# Board.net
KiCad netlist of a schematic drawn in EAGLE
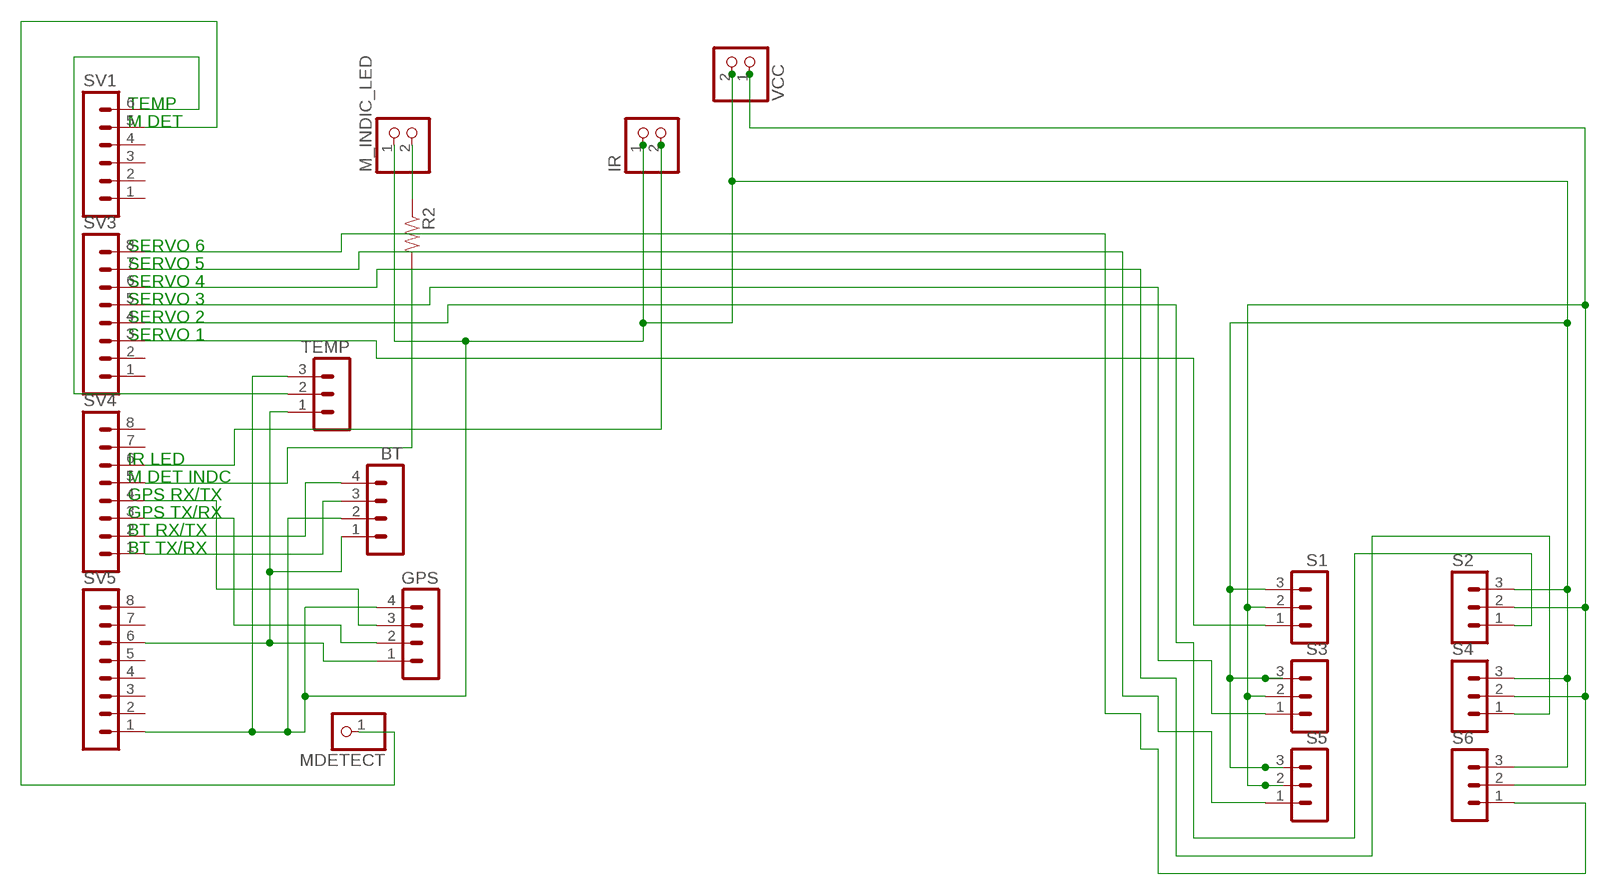
[diagram p0: schematic, sheet 1]

(export (version "E")
  (design (tool "Eeschema 10.0.6"))
  (components
    (comp (ref "BT")
      (value "MA04-1")
      (footprint "eagle-import:MA04-1")
      (libsource (lib "eagle-import") (part "MA04-1"))
    )
    (comp (ref "GPS")
      (value "MA04-1")
      (footprint "eagle-import:MA04-1")
      (libsource (lib "eagle-import") (part "MA04-1"))
    )
    (comp (ref "IR")
      (value "PINHD-1X2")
      (footprint "eagle-import:1X02")
      (libsource (lib "eagle-import") (part "PINHD-1X2"))
    )
    (comp (ref "MDETECT")
      (value "PINHD-1X1")
      (footprint "eagle-import:1X01")
      (libsource (lib "eagle-import") (part "PINHD-1X1"))
    )
    (comp (ref "M_INDIC_LED")
      (value "PINHD-1X2")
      (footprint "eagle-import:1X02")
      (libsource (lib "eagle-import") (part "PINHD-1X2"))
    )
    (comp (ref "R2")
      (value "RESISTORAXIAL-0.3")
      (footprint "eagle-import:AXIAL-0.3")
      (libsource (lib "eagle-import") (part "RESISTORAXIAL-0.3"))
    )
    (comp (ref "S1")
      (value "MA03-1")
      (footprint "eagle-import:MA03-1")
      (libsource (lib "eagle-import") (part "MA03-1"))
    )
    (comp (ref "S2")
      (value "MA03-1")
      (footprint "eagle-import:MA03-1")
      (libsource (lib "eagle-import") (part "MA03-1"))
    )
    (comp (ref "S3")
      (value "MA03-1")
      (footprint "eagle-import:MA03-1")
      (libsource (lib "eagle-import") (part "MA03-1"))
    )
    (comp (ref "S4")
      (value "MA03-1")
      (footprint "eagle-import:MA03-1")
      (libsource (lib "eagle-import") (part "MA03-1"))
    )
    (comp (ref "S5")
      (value "MA03-1")
      (footprint "eagle-import:MA03-1")
      (libsource (lib "eagle-import") (part "MA03-1"))
    )
    (comp (ref "S6")
      (value "MA03-1")
      (footprint "eagle-import:MA03-1")
      (libsource (lib "eagle-import") (part "MA03-1"))
    )
    (comp (ref "SV1")
      (value "MA06-1")
      (footprint "eagle-import:MA06-1")
      (libsource (lib "eagle-import") (part "MA06-1"))
    )
    (comp (ref "SV3")
      (value "MA08-1")
      (footprint "eagle-import:MA08-1")
      (libsource (lib "eagle-import") (part "MA08-1"))
    )
    (comp (ref "SV4")
      (value "MA08-1")
      (footprint "eagle-import:MA08-1")
      (libsource (lib "eagle-import") (part "MA08-1"))
    )
    (comp (ref "SV5")
      (value "MA08-1")
      (footprint "eagle-import:MA08-1")
      (libsource (lib "eagle-import") (part "MA08-1"))
    )
    (comp (ref "TEMP")
      (value "MA03-1")
      (footprint "eagle-import:MA03-1")
      (libsource (lib "eagle-import") (part "MA03-1"))
    )
    (comp (ref "VCC")
      (value "PINHD-1X2")
      (footprint "eagle-import:1X02")
      (libsource (lib "eagle-import") (part "PINHD-1X2"))
    )
  )
  (nets
    (net (code "1") (name "Net-(BT-Pad1)") (class "Default")
      (node (ref "BT") (pin "1") (pinfunction "1_1") (pintype "passive"))
      (node (ref "GPS") (pin "1") (pinfunction "1_1") (pintype "passive"))
      (node (ref "SV5") (pin "6") (pinfunction "6_6") (pintype "passive"))
      (node (ref "TEMP") (pin "1") (pinfunction "1_1") (pintype "passive"))
    )
    (net (code "2") (name "Net-(BT-Pad2)") (class "Default")
      (node (ref "BT") (pin "2") (pinfunction "2_2") (pintype "passive"))
      (node (ref "GPS") (pin "4") (pinfunction "4_4") (pintype "passive"))
      (node (ref "IR") (pin "1") (pinfunction "1_1") (pintype "passive"))
      (node (ref "M_INDIC_LED") (pin "1") (pinfunction "1_1") (pintype "passive"))
      (node (ref "S1") (pin "3") (pinfunction "3_3") (pintype "passive"))
      (node (ref "S2") (pin "3") (pinfunction "3_3") (pintype "passive"))
      (node (ref "S3") (pin "3") (pinfunction "3_3") (pintype "passive"))
      (node (ref "S4") (pin "3") (pinfunction "3_3") (pintype "passive"))
      (node (ref "S5") (pin "3") (pinfunction "3_3") (pintype "passive"))
      (node (ref "S6") (pin "3") (pinfunction "3_3") (pintype "passive"))
      (node (ref "SV5") (pin "1") (pinfunction "1_1") (pintype "passive"))
      (node (ref "TEMP") (pin "3") (pinfunction "3_3") (pintype "passive"))
      (node (ref "VCC") (pin "2") (pinfunction "2_2") (pintype "passive"))
    )
    (net (code "3") (name "Net-(BT-Pad3)") (class "Default")
      (node (ref "BT") (pin "3") (pinfunction "3_3") (pintype "passive"))
      (node (ref "SV4") (pin "1") (pinfunction "1_1") (pintype "passive"))
    )
    (net (code "4") (name "Net-(BT-Pad4)") (class "Default")
      (node (ref "BT") (pin "4") (pinfunction "4_4") (pintype "passive"))
      (node (ref "SV4") (pin "2") (pinfunction "2_2") (pintype "passive"))
    )
    (net (code "5") (name "Net-(GPS-Pad2)") (class "Default")
      (node (ref "GPS") (pin "2") (pinfunction "2_2") (pintype "passive"))
      (node (ref "SV4") (pin "3") (pinfunction "3_3") (pintype "passive"))
    )
    (net (code "6") (name "Net-(GPS-Pad3)") (class "Default")
      (node (ref "GPS") (pin "3") (pinfunction "3_3") (pintype "passive"))
      (node (ref "SV4") (pin "4") (pinfunction "4_4") (pintype "passive"))
    )
    (net (code "7") (name "Net-(IR-Pad2)") (class "Default")
      (node (ref "IR") (pin "2") (pinfunction "2_2") (pintype "passive"))
      (node (ref "SV4") (pin "6") (pinfunction "6_6") (pintype "passive"))
    )
    (net (code "8") (name "Net-(MDETECT-Pad1)") (class "Default")
      (node (ref "MDETECT") (pin "1") (pinfunction "1_1") (pintype "passive"))
      (node (ref "SV1") (pin "5") (pinfunction "5_5") (pintype "passive"))
    )
    (net (code "9") (name "Net-(R2-1)") (class "Default")
      (node (ref "M_INDIC_LED") (pin "2") (pinfunction "2_2") (pintype "passive"))
      (node (ref "R2") (pin "P$1") (pinfunction "1_P$1") (pintype "passive"))
    )
    (net (code "10") (name "Net-(R2-2)") (class "Default")
      (node (ref "R2") (pin "P$2") (pinfunction "2_P$2") (pintype "passive"))
      (node (ref "SV4") (pin "5") (pinfunction "5_5") (pintype "passive"))
    )
    (net (code "11") (name "Net-(S1-Pad1)") (class "Default")
      (node (ref "S1") (pin "1") (pinfunction "1_1") (pintype "passive"))
      (node (ref "SV3") (pin "3") (pinfunction "3_3") (pintype "passive"))
    )
    (net (code "12") (name "Net-(S1-Pad2)") (class "Default")
      (node (ref "S1") (pin "2") (pinfunction "2_2") (pintype "passive"))
      (node (ref "S2") (pin "2") (pinfunction "2_2") (pintype "passive"))
      (node (ref "S3") (pin "2") (pinfunction "2_2") (pintype "passive"))
      (node (ref "S4") (pin "2") (pinfunction "2_2") (pintype "passive"))
      (node (ref "S5") (pin "2") (pinfunction "2_2") (pintype "passive"))
      (node (ref "S6") (pin "2") (pinfunction "2_2") (pintype "passive"))
      (node (ref "VCC") (pin "1") (pinfunction "1_1") (pintype "passive"))
    )
    (net (code "13") (name "Net-(S2-Pad1)") (class "Default")
      (node (ref "S2") (pin "1") (pinfunction "1_1") (pintype "passive"))
      (node (ref "SV3") (pin "4") (pinfunction "4_4") (pintype "passive"))
    )
    (net (code "14") (name "Net-(S3-Pad1)") (class "Default")
      (node (ref "S3") (pin "1") (pinfunction "1_1") (pintype "passive"))
      (node (ref "SV3") (pin "5") (pinfunction "5_5") (pintype "passive"))
    )
    (net (code "15") (name "Net-(S4-Pad1)") (class "Default")
      (node (ref "S4") (pin "1") (pinfunction "1_1") (pintype "passive"))
      (node (ref "SV3") (pin "6") (pinfunction "6_6") (pintype "passive"))
    )
    (net (code "16") (name "Net-(S5-Pad1)") (class "Default")
      (node (ref "S5") (pin "1") (pinfunction "1_1") (pintype "passive"))
      (node (ref "SV3") (pin "7") (pinfunction "7_7") (pintype "passive"))
    )
    (net (code "17") (name "Net-(S6-Pad1)") (class "Default")
      (node (ref "S6") (pin "1") (pinfunction "1_1") (pintype "passive"))
      (node (ref "SV3") (pin "8") (pinfunction "8_8") (pintype "passive"))
    )
    (net (code "18") (name "Net-(SV1-Pad6)") (class "Default")
      (node (ref "SV1") (pin "6") (pinfunction "6_6") (pintype "passive"))
      (node (ref "TEMP") (pin "2") (pinfunction "2_2") (pintype "passive"))
    )
    (net (code "19") (name "unconnected-(SV1-Pad1)") (class "Default")
      (node (ref "SV1") (pin "1") (pinfunction "1_1") (pintype "passive"))
    )
    (net (code "20") (name "unconnected-(SV1-Pad2)") (class "Default")
      (node (ref "SV1") (pin "2") (pinfunction "2_2") (pintype "passive"))
    )
    (net (code "21") (name "unconnected-(SV1-Pad3)") (class "Default")
      (node (ref "SV1") (pin "3") (pinfunction "3_3") (pintype "passive"))
    )
    (net (code "22") (name "unconnected-(SV1-Pad4)") (class "Default")
      (node (ref "SV1") (pin "4") (pinfunction "4_4") (pintype "passive"))
    )
    (net (code "23") (name "unconnected-(SV3-Pad1)") (class "Default")
      (node (ref "SV3") (pin "1") (pinfunction "1_1") (pintype "passive"))
    )
    (net (code "24") (name "unconnected-(SV3-Pad2)") (class "Default")
      (node (ref "SV3") (pin "2") (pinfunction "2_2") (pintype "passive"))
    )
    (net (code "25") (name "unconnected-(SV4-Pad7)") (class "Default")
      (node (ref "SV4") (pin "7") (pinfunction "7_7") (pintype "passive"))
    )
    (net (code "26") (name "unconnected-(SV4-Pad8)") (class "Default")
      (node (ref "SV4") (pin "8") (pinfunction "8_8") (pintype "passive"))
    )
    (net (code "27") (name "unconnected-(SV5-Pad2)") (class "Default")
      (node (ref "SV5") (pin "2") (pinfunction "2_2") (pintype "passive"))
    )
    (net (code "28") (name "unconnected-(SV5-Pad3)") (class "Default")
      (node (ref "SV5") (pin "3") (pinfunction "3_3") (pintype "passive"))
    )
    (net (code "29") (name "unconnected-(SV5-Pad4)") (class "Default")
      (node (ref "SV5") (pin "4") (pinfunction "4_4") (pintype "passive"))
    )
    (net (code "30") (name "unconnected-(SV5-Pad5)") (class "Default")
      (node (ref "SV5") (pin "5") (pinfunction "5_5") (pintype "passive"))
    )
    (net (code "31") (name "unconnected-(SV5-Pad7)") (class "Default")
      (node (ref "SV5") (pin "7") (pinfunction "7_7") (pintype "passive"))
    )
    (net (code "32") (name "unconnected-(SV5-Pad8)") (class "Default")
      (node (ref "SV5") (pin "8") (pinfunction "8_8") (pintype "passive"))
    )
  )
)
